# nbedmbed_minipro_noimu_flipped.net
KiCad netlist of a schematic drawn in EAGLE
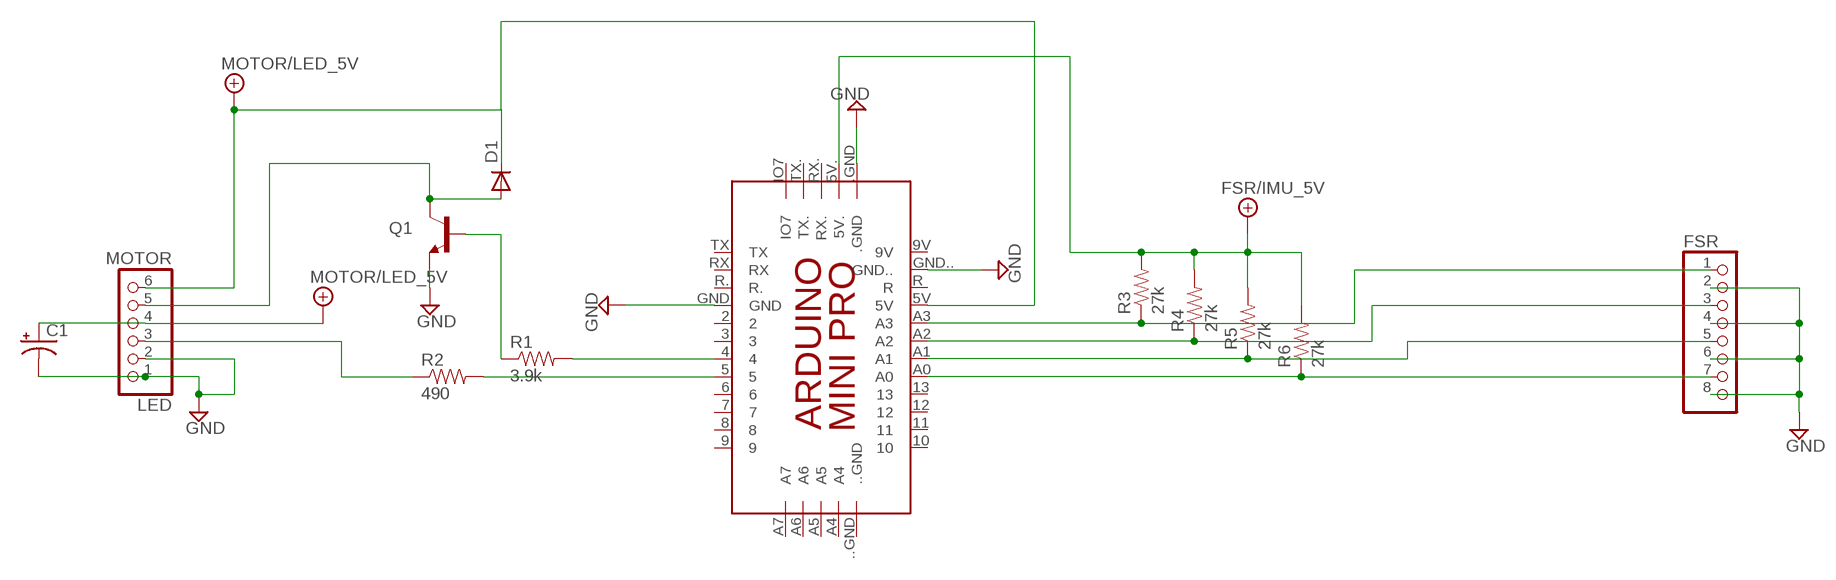
[diagram p0: schematic, sheet 1]

(export (version "E")
  (design (tool "Eeschema 10.0.6"))
  (components
    (comp (ref "C1")
      (value "CAP_POLPTH1")
      (footprint "eagle-import:CPOL-RADIAL-100UF-25V")
      (libsource (lib "eagle-import") (part "CAP_POLPTH1"))
    )
    (comp (ref "D1")
      (value "DIODE1N4148")
      (footprint "eagle-import:DIODE-1N4148")
      (libsource (lib "eagle-import") (part "DIODE1N4148"))
    )
    (comp (ref "FSR")
      (value "PINHD-1X8BIG")
      (footprint "eagle-import:1X08-BIG")
      (libsource (lib "eagle-import") (part "PINHD-1X8BIG"))
    )
    (comp (ref "LED")
      (value "MOTOR")
      (footprint "eagle-import:1X06-BIG")
      (libsource (lib "eagle-import") (part "PINHD-1X6B"))
    )
    (comp (ref "PCB2")
      (value "ARDUINO_MINI_PRO")
      (footprint "eagle-import:ARDUINO_MINI_PRO")
      (libsource (lib "eagle-import") (part "ARDUINO_MINI_PRO"))
    )
    (comp (ref "Q1")
      (value "TRANSISTOR_NPNTO-92-AMMO")
      (footprint "eagle-import:TO-92-AMMO")
      (libsource (lib "eagle-import") (part "TRANSISTOR_NPNTO-92-AMMO"))
    )
    (comp (ref "R1")
      (value "3.9k")
      (footprint "eagle-import:1_6W-RES")
      (libsource (lib "eagle-import") (part "RESISTORPTH-1/6W"))
    )
    (comp (ref "R2")
      (value "490")
      (footprint "eagle-import:1_6W-RES")
      (libsource (lib "eagle-import") (part "RESISTORPTH-1/6W"))
    )
    (comp (ref "R3")
      (value "27k")
      (footprint "eagle-import:1_6W-RES")
      (libsource (lib "eagle-import") (part "RESISTORPTH-1/6W"))
    )
    (comp (ref "R4")
      (value "27k")
      (footprint "eagle-import:1_6W-RES")
      (libsource (lib "eagle-import") (part "RESISTORPTH-1/6W"))
    )
    (comp (ref "R5")
      (value "27k")
      (footprint "eagle-import:1_6W-RES")
      (libsource (lib "eagle-import") (part "RESISTORPTH-1/6W"))
    )
    (comp (ref "R6")
      (value "27k")
      (footprint "eagle-import:1_6W-RES")
      (libsource (lib "eagle-import") (part "RESISTORPTH-1/6W"))
    )
  )
  (nets
    (net (code "1") (name "FSR{slash}IMU_5V") (class "Default")
      (node (ref "PCB2") (pin "5V.") (pinfunction "5V._5V.") (pintype "bidirectional"))
      (node (ref "R3") (pin "2") (pinfunction "2_2") (pintype "passive"))
      (node (ref "R4") (pin "2") (pinfunction "2_2") (pintype "passive"))
      (node (ref "R5") (pin "2") (pinfunction "2_2") (pintype "passive"))
      (node (ref "R6") (pin "2") (pinfunction "2_2") (pintype "passive"))
    )
    (net (code "2") (name "GND") (class "Default")
      (node (ref "C1") (pin "2") (pinfunction "-_2") (pintype "passive"))
      (node (ref "FSR") (pin "2") (pinfunction "2_2") (pintype "passive"))
      (node (ref "FSR") (pin "4") (pinfunction "4_4") (pintype "passive"))
      (node (ref "FSR") (pin "6") (pinfunction "6_6") (pintype "passive"))
      (node (ref "FSR") (pin "8") (pinfunction "8_8") (pintype "passive"))
      (node (ref "LED") (pin "1") (pinfunction "1_1") (pintype "passive"))
      (node (ref "LED") (pin "2") (pinfunction "2_2") (pintype "passive"))
      (node (ref "PCB2") (pin ".GND") (pinfunction ".GND_.GND") (pintype "bidirectional"))
      (node (ref "PCB2") (pin "GND") (pinfunction "GND_GND") (pintype "bidirectional"))
      (node (ref "PCB2") (pin "GND..") (pinfunction "GND.._GND..") (pintype "bidirectional"))
      (node (ref "Q1") (pin "1") (pinfunction "E_1") (pintype "passive"))
    )
    (net (code "3") (name "MOTOR{slash}LED_5V") (class "Default")
      (node (ref "C1") (pin "1") (pinfunction "+_1") (pintype "passive"))
      (node (ref "D1") (pin "C") (pinfunction "C_C") (pintype "passive"))
      (node (ref "LED") (pin "4") (pinfunction "4_4") (pintype "passive"))
      (node (ref "LED") (pin "6") (pinfunction "6_6") (pintype "passive"))
      (node (ref "PCB2") (pin "5V") (pinfunction "5V_5V") (pintype "bidirectional"))
    )
    (net (code "4") (name "Net-(FSR-Pad1)") (class "Default")
      (node (ref "FSR") (pin "1") (pinfunction "1_1") (pintype "passive"))
      (node (ref "PCB2") (pin "A3") (pinfunction "A3_A3") (pintype "bidirectional"))
      (node (ref "R3") (pin "1") (pinfunction "1_1") (pintype "passive"))
    )
    (net (code "5") (name "Net-(FSR-Pad3)") (class "Default")
      (node (ref "FSR") (pin "3") (pinfunction "3_3") (pintype "passive"))
      (node (ref "PCB2") (pin "A2") (pinfunction "A2_A2") (pintype "bidirectional"))
      (node (ref "R4") (pin "1") (pinfunction "1_1") (pintype "passive"))
    )
    (net (code "6") (name "Net-(FSR-Pad5)") (class "Default")
      (node (ref "FSR") (pin "5") (pinfunction "5_5") (pintype "passive"))
      (node (ref "PCB2") (pin "A1") (pinfunction "A1_A1") (pintype "bidirectional"))
      (node (ref "R5") (pin "1") (pinfunction "1_1") (pintype "passive"))
    )
    (net (code "7") (name "Net-(FSR-Pad7)") (class "Default")
      (node (ref "FSR") (pin "7") (pinfunction "7_7") (pintype "passive"))
      (node (ref "PCB2") (pin "A0") (pinfunction "A0_A0") (pintype "bidirectional"))
      (node (ref "R6") (pin "1") (pinfunction "1_1") (pintype "passive"))
    )
    (net (code "8") (name "Net-(LED-Pad3)") (class "Default")
      (node (ref "LED") (pin "3") (pinfunction "3_3") (pintype "passive"))
      (node (ref "R2") (pin "1") (pinfunction "1_1") (pintype "passive"))
    )
    (net (code "9") (name "Net-(PCB2-Pad4)") (class "Default")
      (node (ref "PCB2") (pin "4") (pinfunction "4_4") (pintype "bidirectional"))
      (node (ref "R1") (pin "2") (pinfunction "2_2") (pintype "passive"))
    )
    (net (code "10") (name "Net-(PCB2-Pad5)") (class "Default")
      (node (ref "PCB2") (pin "5") (pinfunction "5_5") (pintype "bidirectional"))
      (node (ref "R2") (pin "2") (pinfunction "2_2") (pintype "passive"))
    )
    (net (code "11") (name "Net-(Q1-B)") (class "Default")
      (node (ref "Q1") (pin "2") (pinfunction "B_2") (pintype "passive"))
      (node (ref "R1") (pin "1") (pinfunction "1_1") (pintype "passive"))
    )
    (net (code "12") (name "Net-(Q1-C)") (class "Default")
      (node (ref "D1") (pin "A") (pinfunction "A_A") (pintype "passive"))
      (node (ref "LED") (pin "5") (pinfunction "5_5") (pintype "passive"))
      (node (ref "Q1") (pin "3") (pinfunction "C_3") (pintype "passive"))
    )
    (net (code "13") (name "unconnected-(PCB2-Pad..GND)") (class "Default")
      (node (ref "PCB2") (pin "..GND") (pinfunction "..GND_..GND") (pintype "bidirectional"))
    )
    (net (code "14") (name "unconnected-(PCB2-Pad2)") (class "Default")
      (node (ref "PCB2") (pin "2") (pinfunction "2_2") (pintype "bidirectional"))
    )
    (net (code "15") (name "unconnected-(PCB2-Pad3)") (class "Default")
      (node (ref "PCB2") (pin "3") (pinfunction "3_3") (pintype "bidirectional"))
    )
    (net (code "16") (name "unconnected-(PCB2-Pad6)") (class "Default")
      (node (ref "PCB2") (pin "6") (pinfunction "6_6") (pintype "bidirectional"))
    )
    (net (code "17") (name "unconnected-(PCB2-Pad7)") (class "Default")
      (node (ref "PCB2") (pin "7") (pinfunction "7_7") (pintype "bidirectional"))
    )
    (net (code "18") (name "unconnected-(PCB2-Pad8)") (class "Default")
      (node (ref "PCB2") (pin "8") (pinfunction "8_8") (pintype "bidirectional"))
    )
    (net (code "19") (name "unconnected-(PCB2-Pad9)") (class "Default")
      (node (ref "PCB2") (pin "9") (pinfunction "9_9") (pintype "bidirectional"))
    )
    (net (code "20") (name "unconnected-(PCB2-Pad9V)") (class "Default")
      (node (ref "PCB2") (pin "9V") (pinfunction "9V_9V") (pintype "bidirectional"))
    )
    (net (code "21") (name "unconnected-(PCB2-Pad10)") (class "Default")
      (node (ref "PCB2") (pin "10") (pinfunction "10_10") (pintype "bidirectional"))
    )
    (net (code "22") (name "unconnected-(PCB2-Pad11)") (class "Default")
      (node (ref "PCB2") (pin "11") (pinfunction "11_11") (pintype "bidirectional"))
    )
    (net (code "23") (name "unconnected-(PCB2-Pad12)") (class "Default")
      (node (ref "PCB2") (pin "12") (pinfunction "12_12") (pintype "bidirectional"))
    )
    (net (code "24") (name "unconnected-(PCB2-Pad13)") (class "Default")
      (node (ref "PCB2") (pin "13") (pinfunction "13_13") (pintype "bidirectional"))
    )
    (net (code "25") (name "unconnected-(PCB2-PadA4)") (class "Default")
      (node (ref "PCB2") (pin "A4") (pinfunction "A4_A4") (pintype "bidirectional"))
    )
    (net (code "26") (name "unconnected-(PCB2-PadA5)") (class "Default")
      (node (ref "PCB2") (pin "A5") (pinfunction "A5_A5") (pintype "bidirectional"))
    )
    (net (code "27") (name "unconnected-(PCB2-PadA6)") (class "Default")
      (node (ref "PCB2") (pin "A6") (pinfunction "A6_A6") (pintype "bidirectional"))
    )
    (net (code "28") (name "unconnected-(PCB2-PadA7)") (class "Default")
      (node (ref "PCB2") (pin "A7") (pinfunction "A7_A7") (pintype "bidirectional"))
    )
    (net (code "29") (name "unconnected-(PCB2-PadIO7)") (class "Default")
      (node (ref "PCB2") (pin "IO7") (pinfunction "IO7_IO7") (pintype "bidirectional"))
    )
    (net (code "30") (name "unconnected-(PCB2-PadR)") (class "Default")
      (node (ref "PCB2") (pin "R") (pinfunction "R_R") (pintype "bidirectional"))
    )
    (net (code "31") (name "unconnected-(PCB2-PadR.)") (class "Default")
      (node (ref "PCB2") (pin "R.") (pinfunction "R._R.") (pintype "bidirectional"))
    )
    (net (code "32") (name "unconnected-(PCB2-PadRX)") (class "Default")
      (node (ref "PCB2") (pin "RX") (pinfunction "RX_RX") (pintype "bidirectional"))
    )
    (net (code "33") (name "unconnected-(PCB2-PadRX.)") (class "Default")
      (node (ref "PCB2") (pin "RX.") (pinfunction "RX._RX.") (pintype "bidirectional"))
    )
    (net (code "34") (name "unconnected-(PCB2-PadTX)") (class "Default")
      (node (ref "PCB2") (pin "TX") (pinfunction "TX_TX") (pintype "bidirectional"))
    )
    (net (code "35") (name "unconnected-(PCB2-PadTX.)") (class "Default")
      (node (ref "PCB2") (pin "TX.") (pinfunction "TX._TX.") (pintype "bidirectional"))
    )
  )
)
